# ARM_CTR.net
KiCad netlist of a schematic drawn in Altium Designer
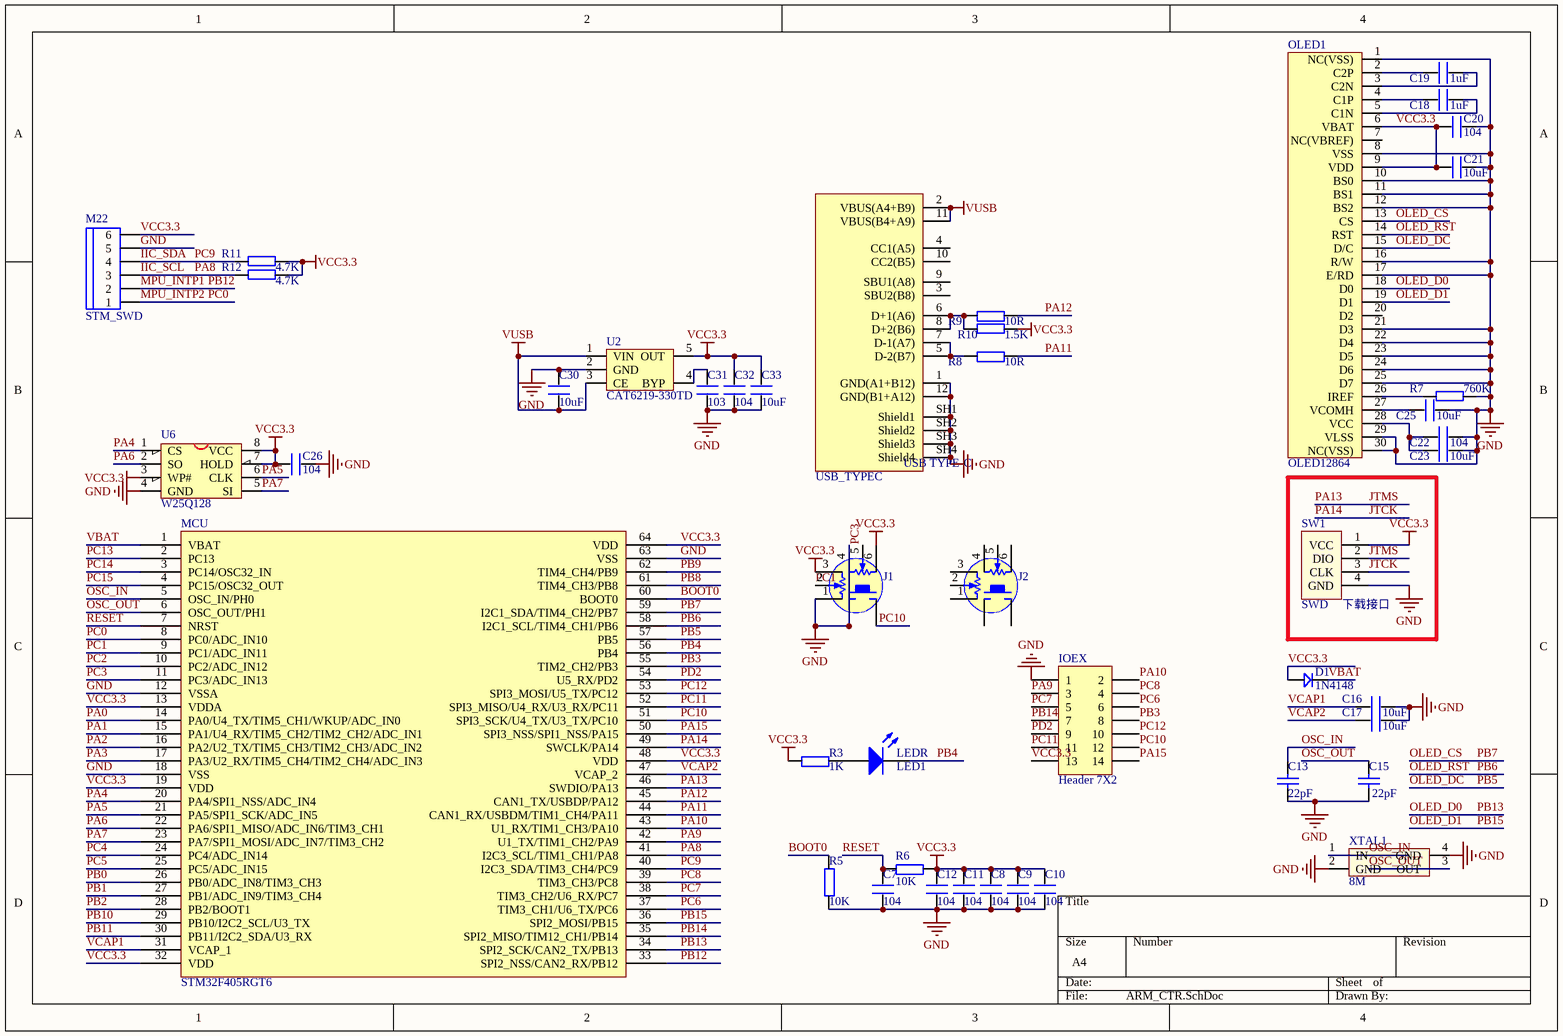
[diagram p0: ARM_CTR.SchDoc]

(export (version "E")
  (design (tool "Eeschema 10.0.6"))
  (components
    (comp (ref "C7")
      (value "104")
      (footprint "C 0603_L")
      (libsource (lib "WarShip V3 STM32103封装库") (part "C"))
    )
    (comp (ref "C8")
      (value "104")
      (footprint "C 0603_L")
      (libsource (lib "WarShip V3 STM32103封装库") (part "C"))
    )
    (comp (ref "C9")
      (value "104")
      (footprint "C 0603_L")
      (libsource (lib "WarShip V3 STM32103封装库") (part "C"))
    )
    (comp (ref "C10")
      (value "104")
      (footprint "C 0603_L")
      (libsource (lib "WarShip V3 STM32103封装库") (part "C"))
    )
    (comp (ref "C11")
      (value "104")
      (footprint "C 0603_L")
      (libsource (lib "WarShip V3 STM32103封装库") (part "C"))
    )
    (comp (ref "C12")
      (value "104")
      (footprint "C 0603_L")
      (libsource (lib "WarShip V3 STM32103封装库") (part "C"))
    )
    (comp (ref "C13") (value "22pF") (footprint "C 0603_L") (libsource (lib "L476") (part "CAP")))
    (comp (ref "C15") (value "22pF") (footprint "C 0603_L") (libsource (lib "L476") (part "CAP")))
    (comp (ref "C16")
      (value "10uF")
      (footprint "C 0603_L")
      (libsource (lib "WarShip V3 STM32103封装库") (part "C"))
    )
    (comp (ref "C17")
      (value "10uF")
      (footprint "C 0603_L")
      (libsource (lib "WarShip V3 STM32103封装库") (part "C"))
    )
    (comp (ref "C18")
      (value "1uF")
      (footprint "C 0603_L")
      (libsource (lib "WarShip V3 STM32103封装库") (part "C"))
    )
    (comp (ref "C19")
      (value "1uF")
      (footprint "C 0603_L")
      (libsource (lib "WarShip V3 STM32103封装库") (part "C"))
    )
    (comp (ref "C20")
      (value "104")
      (footprint "C 0603_L")
      (libsource (lib "WarShip V3 STM32103封装库") (part "C"))
    )
    (comp (ref "C21")
      (value "10uF")
      (footprint "C 0603_L")
      (libsource (lib "WarShip V3 STM32103封装库") (part "C"))
    )
    (comp (ref "C22")
      (value "104")
      (footprint "C 0603_L")
      (libsource (lib "WarShip V3 STM32103封装库") (part "C"))
    )
    (comp (ref "C23")
      (value "10uF")
      (footprint "C 0603_L")
      (libsource (lib "WarShip V3 STM32103封装库") (part "C"))
    )
    (comp (ref "C25")
      (value "10uF")
      (footprint "C 0603_L")
      (libsource (lib "WarShip V3 STM32103封装库") (part "C"))
    )
    (comp (ref "C26")
      (value "104")
      (footprint "C 0603_L")
      (libsource (lib "WarShip V3 STM32103封装库") (part "C"))
    )
    (comp (ref "C30")
      (value "10uF")
      (footprint "C 0603_L")
      (libsource (lib "WarShip V3 STM32103封装库") (part "C"))
    )
    (comp (ref "C31")
      (value "103")
      (footprint "C 0603_L")
      (libsource (lib "WarShip V3 STM32103封装库") (part "C"))
    )
    (comp (ref "C32")
      (value "104")
      (footprint "C 0603_L")
      (libsource (lib "WarShip V3 STM32103封装库") (part "C"))
    )
    (comp (ref "C33")
      (value "10uF")
      (footprint "C 0603_L")
      (libsource (lib "WarShip V3 STM32103封装库") (part "C"))
    )
    (comp (ref "D1")
      (value "1N4148")
      (footprint "二极管-整流桥:SOD-323")
      (libsource (lib "阿波罗STM32F4&F7底板封装库") (part "D"))
    )
    (comp (ref "IOEX")
      (value "Header 7X2")
      (footprint "HDR2.54-LI-2x7P")
      (description "Header, 7-Pin, Dual row")
      (fields (field (name "PUBLISHER") "Altium Limited"))
      (libsource (lib "Miscellaneous Connectors") (part "Header 7X2"))
    )
    (comp (ref "J1")
      (value "方向摇杆")
      (footprint "Joystick")
      (description "摇杆")
      (libsource (lib "REMOTOR") (part "摇杆_1"))
    )
    (comp (ref "J2")
      (value "方向摇杆")
      (footprint "Joystick")
      (description "摇杆")
      (libsource (lib "REMOTOR") (part "摇杆_1"))
    )
    (comp (ref "LEDR")
      (value "LED1")
      (footprint "LED 0805B")
      (description "Typical RED, GREEN, YELLOW, AMBER GaAs LED")
      (fields (field (name "PUBLISHER") "Altium Limited"))
      (libsource (lib "阿波罗STM32F4&F7底板封装库") (part "LED2"))
    )
    (comp (ref "M22") (value "STM_SWD") (footprint "SH1.0-6P") (libsource (lib "MiniFly ") (part "HEAD6")))
    (comp (ref "MCU")
      (value "STM32F405RGT6")
      (footprint "LQFP64 10X10_L")
      (description "Flaah:256/RAM:48/IO:51")
      (libsource (lib "ATKF405 V1.1") (part "STM32F405RGT6"))
    )
    (comp (ref "OLED1")
      (value "OLED12864")
      (footprint "OLED_0.96")
      (libsource (lib "OLED模块封装库") (part "OLED12864"))
    )
    (comp (ref "R3")
      (value "1K")
      (footprint "R 0603_L")
      (libsource (lib "WarShip V3 STM32103封装库") (part "R"))
    )
    (comp (ref "R5")
      (value "10K")
      (footprint "R 0603_L")
      (libsource (lib "WarShip V3 STM32103封装库") (part "R"))
    )
    (comp (ref "R6")
      (value "10K")
      (footprint "R 0603_L")
      (libsource (lib "WarShip V3 STM32103封装库") (part "R"))
    )
    (comp (ref "R7")
      (value "760K")
      (footprint "R 0603_L")
      (libsource (lib "WarShip V3 STM32103封装库") (part "R"))
    )
    (comp (ref "R8")
      (value "10R")
      (footprint "R 0603_L")
      (libsource (lib "WarShip V3 STM32103封装库") (part "R"))
    )
    (comp (ref "R9")
      (value "10R")
      (footprint "R 0603_L")
      (libsource (lib "WarShip V3 STM32103封装库") (part "R"))
    )
    (comp (ref "R10")
      (value "1.5K")
      (footprint "R 0603_L")
      (libsource (lib "WarShip V3 STM32103封装库") (part "R"))
    )
    (comp (ref "R11")
      (value "4.7K")
      (footprint "R 0603_L")
      (libsource (lib "WarShip V3 STM32103封装库") (part "R"))
    )
    (comp (ref "R12")
      (value "4.7K")
      (footprint "R 0603_L")
      (libsource (lib "WarShip V3 STM32103封装库") (part "R"))
    )
    (comp (ref "SW1") (value "SWD") (footprint "HDR2.54-LI-4P") (libsource (lib "USBTOOL") (part "SWD")))
    (comp (ref "U2")
      (value "CAT6219-330TD")
      (footprint "SOT23-5L")
      (description "3.3V 500mA LDO")
      (libsource (lib "STM32H743核心板封装库") (part "CAT6219-330TD"))
    )
    (comp (ref "U6")
      (value "W25Q128")
      (footprint "SOP8W_L")
      (description "W25X16;SST25VF016;MX25L1605")
      (libsource (lib "WarShip V3 STM32103封装库") (part "W25X16"))
    )
    (comp (ref "USB_TYPEC")
      (value "USB TypeC")
      (footprint "USB Type-C")
      (description "12P TypeC 母座")
      (libsource (lib "ESP32_Weather") (part "USB Type-C"))
    )
    (comp (ref "XTAL1")
      (value "8M")
      (footprint "XTAL3225   无源")
      (description "无源贴片晶振")
      (libsource (lib "REMOTOR") (part "XTAL-无源贴片"))
    )
  )
  (nets
    (net (code "1") (name "/BOOT0") (class "Default")
      (node (ref "MCU") (pin "60") (pinfunction "BOOT0_60") (pintype "passive"))
      (node (ref "R5") (pin "2") (pintype "passive"))
    )
    (net (code "2") (name "/IIC_SCL") (class "Default")
      (node (ref "M22") (pin "3") (pinfunction "3_3") (pintype "passive"))
      (node (ref "MCU") (pin "41") (pinfunction "I2C3_SCL/TIM1_CH1/PA8_41") (pintype "passive"))
      (node (ref "R12") (pin "2") (pintype "passive"))
    )
    (net (code "3") (name "/IIC_SDA") (class "Default")
      (node (ref "M22") (pin "4") (pinfunction "4_4") (pintype "passive"))
      (node (ref "MCU") (pin "40") (pinfunction "I2C3_SDA/TIM3_CH4/PC9_40") (pintype "passive"))
      (node (ref "R11") (pin "2") (pintype "passive"))
    )
    (net (code "4") (name "/JTCK") (class "Default")
      (node (ref "MCU") (pin "49") (pinfunction "SWCLK/PA14_49") (pintype "passive"))
      (node (ref "SW1") (pin "3") (pinfunction "CLK_3") (pintype "passive"))
    )
    (net (code "5") (name "/JTMS") (class "Default")
      (node (ref "MCU") (pin "46") (pinfunction "SWDIO/PA13_46") (pintype "passive"))
      (node (ref "SW1") (pin "2") (pinfunction "DIO_2") (pintype "passive"))
    )
    (net (code "6") (name "/MPU_INTP1") (class "Default")
      (node (ref "M22") (pin "2") (pinfunction "2_2") (pintype "passive"))
      (node (ref "MCU") (pin "33") (pinfunction "SPI2_NSS/CAN2_RX/PB12_33") (pintype "passive"))
    )
    (net (code "7") (name "/MPU_INTP2") (class "Default")
      (node (ref "M22") (pin "1") (pinfunction "1_1") (pintype "passive"))
      (node (ref "MCU") (pin "8") (pinfunction "PC0/ADC_IN10_8") (pintype "passive"))
    )
    (net (code "8") (name "/OLED_CS") (class "Default")
      (node (ref "MCU") (pin "59") (pinfunction "I2C1_SDA/TIM4_CH2/PB7_59") (pintype "passive"))
      (node (ref "OLED1") (pin "13") (pinfunction "CS_13") (pintype "passive"))
    )
    (net (code "9") (name "/OLED_D0") (class "Default")
      (node (ref "MCU") (pin "34") (pinfunction "SPI2_SCK/CAN2_TX/PB13_34") (pintype "passive"))
      (node (ref "OLED1") (pin "18") (pinfunction "D0_18") (pintype "passive"))
    )
    (net (code "10") (name "/OLED_D1") (class "Default")
      (node (ref "MCU") (pin "36") (pinfunction "SPI2_MOSI/PB15_36") (pintype "passive"))
      (node (ref "OLED1") (pin "19") (pinfunction "D1_19") (pintype "passive"))
    )
    (net (code "11") (name "/OLED_DC") (class "Default")
      (node (ref "MCU") (pin "57") (pinfunction "PB5_57") (pintype "passive"))
      (node (ref "OLED1") (pin "15") (pinfunction "D/C_15") (pintype "passive"))
    )
    (net (code "12") (name "/OLED_RST") (class "Default")
      (node (ref "MCU") (pin "58") (pinfunction "I2C1_SCL/TIM4_CH1/PB6_58") (pintype "passive"))
      (node (ref "OLED1") (pin "14") (pinfunction "RST_14") (pintype "passive"))
    )
    (net (code "13") (name "/OSC_IN") (class "Default")
      (node (ref "C13") (pin "2") (pinfunction "2_2") (pintype "passive"))
      (node (ref "MCU") (pin "5") (pinfunction "OSC_IN/PH0_5") (pintype "passive"))
      (node (ref "XTAL1") (pin "1") (pinfunction "IN_1") (pintype "passive"))
    )
    (net (code "14") (name "/OSC_OUT") (class "Default")
      (node (ref "C15") (pin "2") (pinfunction "2_2") (pintype "passive"))
      (node (ref "MCU") (pin "6") (pinfunction "OSC_OUT/PH1_6") (pintype "passive"))
      (node (ref "XTAL1") (pin "3") (pinfunction "OUT_3") (pintype "passive"))
    )
    (net (code "15") (name "/PA0") (class "Default")
      (node (ref "MCU") (pin "14") (pinfunction "PA0/U4_TX/TIM5_CH1/WKUP/ADC_IN0_14") (pintype "passive"))
    )
    (net (code "16") (name "/PA1") (class "Default")
      (node (ref "MCU") (pin "15") (pinfunction "PA1/U4_RX/TIM5_CH2/TIM2_CH2/ADC_IN1_15") (pintype "passive"))
    )
    (net (code "17") (name "/PA2") (class "Default")
      (node (ref "MCU") (pin "16") (pinfunction "PA2/U2_TX/TIM5_CH3/TIM2_CH3/ADC_IN2_16") (pintype "passive"))
    )
    (net (code "18") (name "/PA3") (class "Default")
      (node (ref "MCU") (pin "17") (pinfunction "PA3/U2_RX/TIM5_CH4/TIM2_CH4/ADC_IN3_17") (pintype "passive"))
    )
    (net (code "19") (name "/PA4") (class "Default")
      (node (ref "MCU") (pin "20") (pinfunction "PA4/SPI1_NSS/ADC_IN4_20") (pintype "passive"))
      (node (ref "U6") (pin "1") (pinfunction "CS_1") (pintype "passive"))
    )
    (net (code "20") (name "/PA5") (class "Default")
      (node (ref "MCU") (pin "21") (pinfunction "PA5/SPI1_SCK/ADC_IN5_21") (pintype "passive"))
      (node (ref "U6") (pin "6") (pinfunction "CLK_6") (pintype "passive"))
    )
    (net (code "21") (name "/PA6") (class "Default")
      (node (ref "MCU") (pin "22") (pinfunction "PA6/SPI1_MISO/ADC_IN6/TIM3_CH1_22") (pintype "passive"))
      (node (ref "U6") (pin "2") (pinfunction "SO_2") (pintype "passive"))
    )
    (net (code "22") (name "/PA7") (class "Default")
      (node (ref "MCU") (pin "23") (pinfunction "PA7/SPI1_MOSI/ADC_IN7/TIM3_CH2_23") (pintype "passive"))
      (node (ref "U6") (pin "5") (pinfunction "SI_5") (pintype "passive"))
    )
    (net (code "23") (name "/PA9") (class "Default")
      (node (ref "IOEX") (pin "3") (pinfunction "3_3") (pintype "passive"))
      (node (ref "MCU") (pin "42") (pinfunction "U1_TX/TIM1_CH2/PA9_42") (pintype "passive"))
    )
    (net (code "24") (name "/PA10") (class "Default")
      (node (ref "IOEX") (pin "2") (pinfunction "2_2") (pintype "passive"))
      (node (ref "MCU") (pin "43") (pinfunction "U1_RX/TIM1_CH3/PA10_43") (pintype "passive"))
    )
    (net (code "25") (name "/PA11") (class "Default")
      (node (ref "MCU") (pin "44") (pinfunction "CAN1_RX/USBDM/TIM1_CH4/PA11_44") (pintype "passive"))
      (node (ref "R8") (pin "2") (pintype "passive"))
    )
    (net (code "26") (name "/PA12") (class "Default")
      (node (ref "MCU") (pin "45") (pinfunction "CAN1_TX/USBDP/PA12_45") (pintype "passive"))
      (node (ref "R9") (pin "2") (pintype "passive"))
    )
    (net (code "27") (name "/PA15") (class "Default")
      (node (ref "IOEX") (pin "14") (pinfunction "14_14") (pintype "passive"))
      (node (ref "MCU") (pin "50") (pinfunction "SPI3_NSS/SPI1_NSS/PA15_50") (pintype "passive"))
    )
    (net (code "28") (name "/PB0") (class "Default")
      (node (ref "MCU") (pin "26") (pinfunction "PB0/ADC_IN8/TIM3_CH3_26") (pintype "passive"))
    )
    (net (code "29") (name "/PB1") (class "Default")
      (node (ref "MCU") (pin "27") (pinfunction "PB1/ADC_IN9/TIM3_CH4_27") (pintype "passive"))
    )
    (net (code "30") (name "/PB2") (class "Default")
      (node (ref "MCU") (pin "28") (pinfunction "PB2/BOOT1_28") (pintype "passive"))
    )
    (net (code "31") (name "/PB3") (class "Default")
      (node (ref "IOEX") (pin "8") (pinfunction "8_8") (pintype "passive"))
      (node (ref "MCU") (pin "55") (pinfunction "TIM2_CH2/PB3_55") (pintype "passive"))
    )
    (net (code "32") (name "/PB4") (class "Default")
      (node (ref "LEDR") (pin "2") (pinfunction "K_2") (pintype "passive"))
      (node (ref "MCU") (pin "56") (pinfunction "PB4_56") (pintype "passive"))
    )
    (net (code "33") (name "/PB8") (class "Default")
      (node (ref "MCU") (pin "61") (pinfunction "TIM4_CH3/PB8_61") (pintype "passive"))
    )
    (net (code "34") (name "/PB9") (class "Default")
      (node (ref "MCU") (pin "62") (pinfunction "TIM4_CH4/PB9_62") (pintype "passive"))
    )
    (net (code "35") (name "/PB10") (class "Default")
      (node (ref "MCU") (pin "29") (pinfunction "PB10/I2C2_SCL/U3_TX_29") (pintype "passive"))
    )
    (net (code "36") (name "/PB11") (class "Default")
      (node (ref "MCU") (pin "30") (pinfunction "PB11/I2C2_SDA/U3_RX_30") (pintype "passive"))
    )
    (net (code "37") (name "/PB14") (class "Default")
      (node (ref "IOEX") (pin "7") (pinfunction "7_7") (pintype "passive"))
      (node (ref "MCU") (pin "35") (pinfunction "SPI2_MISO/TIM12_CH1/PB14_35") (pintype "passive"))
    )
    (net (code "38") (name "/PC1") (class "Default")
      (node (ref "J1") (pin "2") (pinfunction "2_2") (pintype "passive"))
      (node (ref "MCU") (pin "9") (pinfunction "PC1/ADC_IN11_9") (pintype "passive"))
    )
    (net (code "39") (name "/PC2") (class "Default")
      (node (ref "MCU") (pin "10") (pinfunction "PC2/ADC_IN12_10") (pintype "passive"))
    )
    (net (code "40") (name "/PC3") (class "Default")
      (node (ref "J1") (pin "5") (pinfunction "5_5") (pintype "passive"))
      (node (ref "MCU") (pin "11") (pinfunction "PC3/ADC_IN13_11") (pintype "passive"))
    )
    (net (code "41") (name "/PC4") (class "Default")
      (node (ref "MCU") (pin "24") (pinfunction "PC4/ADC_IN14_24") (pintype "passive"))
    )
    (net (code "42") (name "/PC5") (class "Default")
      (node (ref "MCU") (pin "25") (pinfunction "PC5/ADC_IN15_25") (pintype "passive"))
    )
    (net (code "43") (name "/PC6") (class "Default")
      (node (ref "IOEX") (pin "6") (pinfunction "6_6") (pintype "passive"))
      (node (ref "MCU") (pin "37") (pinfunction "TIM3_CH1/U6_TX/PC6_37") (pintype "passive"))
    )
    (net (code "44") (name "/PC7") (class "Default")
      (node (ref "IOEX") (pin "5") (pinfunction "5_5") (pintype "passive"))
      (node (ref "MCU") (pin "38") (pinfunction "TIM3_CH2/U6_RX/PC7_38") (pintype "passive"))
    )
    (net (code "45") (name "/PC8") (class "Default")
      (node (ref "IOEX") (pin "4") (pinfunction "4_4") (pintype "passive"))
      (node (ref "MCU") (pin "39") (pinfunction "TIM3_CH3/PC8_39") (pintype "passive"))
    )
    (net (code "46") (name "/PC10") (class "Default")
      (node (ref "IOEX") (pin "12") (pinfunction "12_12") (pintype "passive"))
      (node (ref "J1") (pin "J1") (pinfunction "J1_J1") (pintype "passive"))
      (node (ref "MCU") (pin "51") (pinfunction "SPI3_SCK/U4_TX/U3_TX/PC10_51") (pintype "passive"))
    )
    (net (code "47") (name "/PC11") (class "Default")
      (node (ref "IOEX") (pin "11") (pinfunction "11_11") (pintype "passive"))
      (node (ref "MCU") (pin "52") (pinfunction "SPI3_MISO/U4_RX/U3_RX/PC11_52") (pintype "passive"))
    )
    (net (code "48") (name "/PC12") (class "Default")
      (node (ref "IOEX") (pin "10") (pinfunction "10_10") (pintype "passive"))
      (node (ref "MCU") (pin "53") (pinfunction "SPI3_MOSI/U5_TX/PC12_53") (pintype "passive"))
    )
    (net (code "49") (name "/PC13") (class "Default")
      (node (ref "MCU") (pin "2") (pinfunction "PC13_2") (pintype "passive"))
    )
    (net (code "50") (name "/PC14") (class "Default")
      (node (ref "MCU") (pin "3") (pinfunction "PC14/OSC32_IN_3") (pintype "passive"))
    )
    (net (code "51") (name "/PC15") (class "Default")
      (node (ref "MCU") (pin "4") (pinfunction "PC15/OSC32_OUT_4") (pintype "passive"))
    )
    (net (code "52") (name "/PD2") (class "Default")
      (node (ref "IOEX") (pin "9") (pinfunction "9_9") (pintype "passive"))
      (node (ref "MCU") (pin "54") (pinfunction "U5_RX/PD2_54") (pintype "passive"))
    )
    (net (code "53") (name "/RESET") (class "Default")
      (node (ref "C7") (pin "2") (pintype "passive"))
      (node (ref "MCU") (pin "7") (pinfunction "NRST_7") (pintype "passive"))
      (node (ref "R6") (pin "1") (pintype "passive"))
    )
    (net (code "54") (name "/VBAT") (class "Default")
      (node (ref "D1") (pin "2") (pintype "passive"))
      (node (ref "MCU") (pin "1") (pinfunction "VBAT_1") (pintype "passive"))
    )
    (net (code "55") (name "/VCAP1") (class "Default")
      (node (ref "C16") (pin "2") (pintype "passive"))
      (node (ref "MCU") (pin "31") (pinfunction "VCAP_1_31") (pintype "passive"))
    )
    (net (code "56") (name "/VCAP2") (class "Default")
      (node (ref "C17") (pin "2") (pintype "passive"))
      (node (ref "MCU") (pin "47") (pinfunction "VCAP_2_47") (pintype "passive"))
    )
    (net (code "57") (name "GND") (class "Default")
      (node (ref "C10") (pin "1") (pintype "passive"))
      (node (ref "C11") (pin "1") (pintype "passive"))
      (node (ref "C12") (pin "1") (pintype "passive"))
      (node (ref "C13") (pin "1") (pinfunction "1_1") (pintype "passive"))
      (node (ref "C15") (pin "1") (pinfunction "1_1") (pintype "passive"))
      (node (ref "C16") (pin "1") (pintype "passive"))
      (node (ref "C17") (pin "1") (pintype "passive"))
      (node (ref "C20") (pin "1") (pintype "passive"))
      (node (ref "C21") (pin "1") (pintype "passive"))
      (node (ref "C22") (pin "1") (pintype "passive"))
      (node (ref "C23") (pin "1") (pintype "passive"))
      (node (ref "C25") (pin "1") (pintype "passive"))
      (node (ref "C26") (pin "2") (pintype "passive"))
      (node (ref "C30") (pin "2") (pintype "passive"))
      (node (ref "C31") (pin "1") (pintype "passive"))
      (node (ref "C32") (pin "1") (pintype "passive"))
      (node (ref "C33") (pin "1") (pintype "passive"))
      (node (ref "C7") (pin "1") (pintype "passive"))
      (node (ref "C8") (pin "1") (pintype "passive"))
      (node (ref "C9") (pin "1") (pintype "passive"))
      (node (ref "IOEX") (pin "1") (pinfunction "1_1") (pintype "passive"))
      (node (ref "J1") (pin "1") (pinfunction "1_1") (pintype "passive"))
      (node (ref "J1") (pin "4") (pinfunction "4_4") (pintype "passive"))
      (node (ref "J1") (pin "J2") (pinfunction "J2_J2") (pintype "passive"))
      (node (ref "M22") (pin "5") (pinfunction "5_5") (pintype "passive"))
      (node (ref "MCU") (pin "12") (pinfunction "VSSA_12") (pintype "passive"))
      (node (ref "MCU") (pin "18") (pinfunction "VSS_18") (pintype "passive"))
      (node (ref "MCU") (pin "63") (pinfunction "VSS_63") (pintype "passive"))
      (node (ref "OLED1") (pin "1") (pinfunction "NC(VSS)_1") (pintype "passive"))
      (node (ref "OLED1") (pin "10") (pinfunction "BS0_10") (pintype "passive"))
      (node (ref "OLED1") (pin "11") (pinfunction "BS1_11") (pintype "passive"))
      (node (ref "OLED1") (pin "12") (pinfunction "BS2_12") (pintype "passive"))
      (node (ref "OLED1") (pin "16") (pinfunction "R/W_16") (pintype "passive"))
      (node (ref "OLED1") (pin "17") (pinfunction "E/RD_17") (pintype "passive"))
      (node (ref "OLED1") (pin "21") (pinfunction "D3_21") (pintype "passive"))
      (node (ref "OLED1") (pin "22") (pinfunction "D4_22") (pintype "passive"))
      (node (ref "OLED1") (pin "23") (pinfunction "D5_23") (pintype "passive"))
      (node (ref "OLED1") (pin "24") (pinfunction "D6_24") (pintype "passive"))
      (node (ref "OLED1") (pin "25") (pinfunction "D7_25") (pintype "passive"))
      (node (ref "OLED1") (pin "29") (pinfunction "VLSS_29") (pintype "passive"))
      (node (ref "OLED1") (pin "30") (pinfunction "NC(VSS)_30") (pintype "passive"))
      (node (ref "OLED1") (pin "8") (pinfunction "VSS_8") (pintype "passive"))
      (node (ref "R5") (pin "1") (pintype "passive"))
      (node (ref "R7") (pin "1") (pintype "passive"))
      (node (ref "SW1") (pin "4") (pinfunction "GND_4") (pintype "passive"))
      (node (ref "U2") (pin "2") (pinfunction "GND_2") (pintype "passive"))
      (node (ref "U6") (pin "4") (pinfunction "GND_4") (pintype "passive"))
      (node (ref "USB_TYPEC") (pin "1") (pinfunction "GND(A1+B12)_1") (pintype "passive"))
      (node (ref "USB_TYPEC") (pin "12") (pinfunction "GND(B1+A12)_12") (pintype "passive"))
      (node (ref "USB_TYPEC") (pin "SH1") (pinfunction "Shield1_SH1") (pintype "passive"))
      (node (ref "USB_TYPEC") (pin "SH2") (pinfunction "Shield2_SH2") (pintype "passive"))
      (node (ref "USB_TYPEC") (pin "SH3") (pinfunction "Shield3_SH3") (pintype "passive"))
      (node (ref "USB_TYPEC") (pin "SH4") (pinfunction "Shield4_SH4") (pintype "passive"))
      (node (ref "XTAL1") (pin "2") (pinfunction "GND_2") (pintype "passive"))
      (node (ref "XTAL1") (pin "4") (pinfunction "GND_4") (pintype "passive"))
    )
    (net (code "58") (name "Net-(LEDR-A)") (class "Default")
      (node (ref "LEDR") (pin "1") (pinfunction "A_1") (pintype "passive"))
      (node (ref "R3") (pin "2") (pintype "passive"))
    )
    (net (code "59") (name "Net-(OLED1-C1N)") (class "Default")
      (node (ref "C18") (pin "1") (pintype "passive"))
      (node (ref "OLED1") (pin "5") (pinfunction "C1N_5") (pintype "passive"))
    )
    (net (code "60") (name "Net-(OLED1-C1P)") (class "Default")
      (node (ref "C18") (pin "2") (pintype "passive"))
      (node (ref "OLED1") (pin "4") (pinfunction "C1P_4") (pintype "passive"))
    )
    (net (code "61") (name "Net-(OLED1-C2N)") (class "Default")
      (node (ref "C19") (pin "1") (pintype "passive"))
      (node (ref "OLED1") (pin "3") (pinfunction "C2N_3") (pintype "passive"))
    )
    (net (code "62") (name "Net-(OLED1-C2P)") (class "Default")
      (node (ref "C19") (pin "2") (pintype "passive"))
      (node (ref "OLED1") (pin "2") (pinfunction "C2P_2") (pintype "passive"))
    )
    (net (code "63") (name "Net-(OLED1-IREF)") (class "Default")
      (node (ref "OLED1") (pin "26") (pinfunction "IREF_26") (pintype "passive"))
      (node (ref "R7") (pin "2") (pintype "passive"))
    )
    (net (code "64") (name "Net-(OLED1-VCC)") (class "Default")
      (node (ref "C22") (pin "2") (pintype "passive"))
      (node (ref "C23") (pin "2") (pintype "passive"))
      (node (ref "OLED1") (pin "28") (pinfunction "VCC_28") (pintype "passive"))
    )
    (net (code "65") (name "Net-(OLED1-VCOMH)") (class "Default")
      (node (ref "C25") (pin "2") (pintype "passive"))
      (node (ref "OLED1") (pin "27") (pinfunction "VCOMH_27") (pintype "passive"))
    )
    (net (code "66") (name "Net-(U2-BYP)") (class "Default")
      (node (ref "C31") (pin "2") (pintype "passive"))
      (node (ref "U2") (pin "4") (pinfunction "BYP_4") (pintype "passive"))
    )
    (net (code "67") (name "Net-(USB_TYPEC-D+1(A6))") (class "Default")
      (node (ref "R10") (pin "2") (pintype "passive"))
      (node (ref "R9") (pin "1") (pintype "passive"))
      (node (ref "USB_TYPEC") (pin "6") (pinfunction "D+1(A6)_6") (pintype "passive"))
      (node (ref "USB_TYPEC") (pin "8") (pinfunction "D+2(B6)_8") (pintype "passive"))
    )
    (net (code "68") (name "Net-(USB_TYPEC-D-1(A7))") (class "Default")
      (node (ref "R8") (pin "1") (pintype "passive"))
      (node (ref "USB_TYPEC") (pin "5") (pinfunction "D-2(B7)_5") (pintype "passive"))
      (node (ref "USB_TYPEC") (pin "7") (pinfunction "D-1(A7)_7") (pintype "passive"))
    )
    (net (code "69") (name "VCC3.3") (class "Default")
      (node (ref "C10") (pin "2") (pintype "passive"))
      (node (ref "C11") (pin "2") (pintype "passive"))
      (node (ref "C12") (pin "2") (pintype "passive"))
      (node (ref "C20") (pin "2") (pintype "passive"))
      (node (ref "C21") (pin "2") (pintype "passive"))
      (node (ref "C26") (pin "1") (pintype "passive"))
      (node (ref "C32") (pin "2") (pintype "passive"))
      (node (ref "C33") (pin "2") (pintype "passive"))
      (node (ref "C8") (pin "2") (pintype "passive"))
      (node (ref "C9") (pin "2") (pintype "passive"))
      (node (ref "D1") (pin "1") (pintype "passive"))
      (node (ref "IOEX") (pin "13") (pinfunction "13_13") (pintype "passive"))
      (node (ref "J1") (pin "3") (pinfunction "3_3") (pintype "passive"))
      (node (ref "J1") (pin "6") (pinfunction "6_6") (pintype "passive"))
      (node (ref "M22") (pin "6") (pinfunction "6_6") (pintype "passive"))
      (node (ref "MCU") (pin "13") (pinfunction "VDDA_13") (pintype "passive"))
      (node (ref "MCU") (pin "19") (pinfunction "VDD_19") (pintype "passive"))
      (node (ref "MCU") (pin "32") (pinfunction "VDD_32") (pintype "passive"))
      (node (ref "MCU") (pin "48") (pinfunction "VDD_48") (pintype "passive"))
      (node (ref "MCU") (pin "64") (pinfunction "VDD_64") (pintype "passive"))
      (node (ref "OLED1") (pin "6") (pinfunction "VBAT_6") (pintype "passive"))
      (node (ref "OLED1") (pin "9") (pinfunction "VDD_9") (pintype "passive"))
      (node (ref "R10") (pin "1") (pintype "passive"))
      (node (ref "R11") (pin "1") (pintype "passive"))
      (node (ref "R12") (pin "1") (pintype "passive"))
      (node (ref "R3") (pin "1") (pintype "passive"))
      (node (ref "R6") (pin "2") (pintype "passive"))
      (node (ref "SW1") (pin "1") (pinfunction "VCC_1") (pintype "passive"))
      (node (ref "U2") (pin "5") (pinfunction "OUT_5") (pintype "passive"))
      (node (ref "U6") (pin "3") (pinfunction "WP#_3") (pintype "passive"))
      (node (ref "U6") (pin "7") (pinfunction "HOLD_7") (pintype "passive"))
      (node (ref "U6") (pin "8") (pinfunction "VCC_8") (pintype "passive"))
    )
    (net (code "70") (name "VUSB") (class "Default")
      (node (ref "C30") (pin "1") (pintype "passive"))
      (node (ref "U2") (pin "1") (pinfunction "VIN_1") (pintype "passive"))
      (node (ref "U2") (pin "3") (pinfunction "CE_3") (pintype "passive"))
      (node (ref "USB_TYPEC") (pin "11") (pinfunction "VBUS(B4+A9)_11") (pintype "passive"))
      (node (ref "USB_TYPEC") (pin "2") (pinfunction "VBUS(A4+B9)_2") (pintype "passive"))
    )
    (net (code "71") (name "unconnected-(J2-Pad1)") (class "Default")
      (node (ref "J2") (pin "1") (pinfunction "1_1") (pintype "passive"))
    )
    (net (code "72") (name "unconnected-(J2-Pad2)") (class "Default")
      (node (ref "J2") (pin "2") (pinfunction "2_2") (pintype "passive"))
    )
    (net (code "73") (name "unconnected-(J2-Pad3)") (class "Default")
      (node (ref "J2") (pin "3") (pinfunction "3_3") (pintype "passive"))
    )
    (net (code "74") (name "unconnected-(J2-Pad4)") (class "Default")
      (node (ref "J2") (pin "4") (pinfunction "4_4") (pintype "passive"))
    )
    (net (code "75") (name "unconnected-(J2-Pad5)") (class "Default")
      (node (ref "J2") (pin "5") (pinfunction "5_5") (pintype "passive"))
    )
    (net (code "76") (name "unconnected-(J2-Pad6)") (class "Default")
      (node (ref "J2") (pin "6") (pinfunction "6_6") (pintype "passive"))
    )
    (net (code "77") (name "unconnected-(J2-PadJ1)") (class "Default")
      (node (ref "J2") (pin "J1") (pinfunction "J1_J1") (pintype "passive"))
    )
    (net (code "78") (name "unconnected-(J2-PadJ2)") (class "Default")
      (node (ref "J2") (pin "J2") (pinfunction "J2_J2") (pintype "passive"))
    )
    (net (code "79") (name "unconnected-(OLED1-D2-Pad20)") (class "Default")
      (node (ref "OLED1") (pin "20") (pinfunction "D2_20") (pintype "passive"))
    )
    (net (code "80") (name "unconnected-(OLED1-NC(VBREF)-Pad7)") (class "Default")
      (node (ref "OLED1") (pin "7") (pinfunction "NC(VBREF)_7") (pintype "passive"))
    )
    (net (code "81") (name "unconnected-(USB_TYPEC-CC1(A5)-Pad4)") (class "Default")
      (node (ref "USB_TYPEC") (pin "4") (pinfunction "CC1(A5)_4") (pintype "passive"))
    )
    (net (code "82") (name "unconnected-(USB_TYPEC-CC2(B5)-Pad10)") (class "Default")
      (node (ref "USB_TYPEC") (pin "10") (pinfunction "CC2(B5)_10") (pintype "passive"))
    )
    (net (code "83") (name "unconnected-(USB_TYPEC-SBU1(A8)-Pad9)") (class "Default")
      (node (ref "USB_TYPEC") (pin "9") (pinfunction "SBU1(A8)_9") (pintype "passive"))
    )
    (net (code "84") (name "unconnected-(USB_TYPEC-SBU2(B8)-Pad3)") (class "Default")
      (node (ref "USB_TYPEC") (pin "3") (pinfunction "SBU2(B8)_3") (pintype "passive"))
    )
  )
)
